# 11_PWR_SYS.net
KiCad netlist of a schematic drawn in Altium Designer
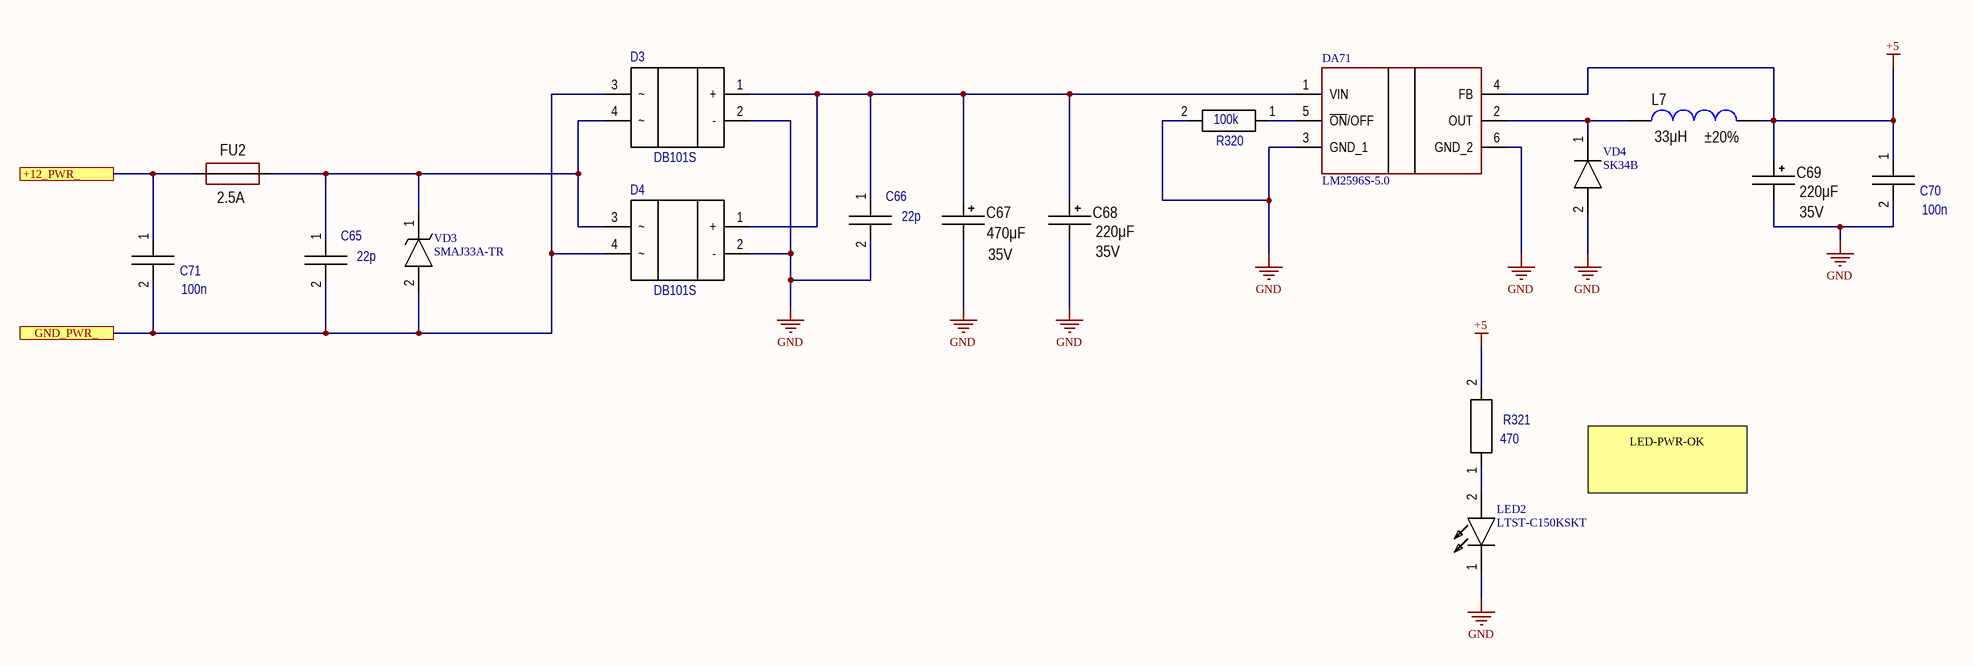
[diagram p0: 11_PWR_SYS.SchDoc]

(export (version "E")
  (design (tool "Eeschema 10.0.6"))
  (components
    (comp (ref "C65")
      (value "22p")
      (footprint "C0603")
      (fields
        (field (name "PART NUMBER") "GRM1885C1H220JA01D")
        (field (name "TOLERANCE") "±5%")
        (field (name "MANUFACTURER") "Murata Manufacturing")
      )
      (libsource (lib "AccessLibrary") (part "Capacitor"))
    )
    (comp (ref "C66")
      (value "22p")
      (footprint "C0603")
      (fields
        (field (name "PART NUMBER") "GRM1885C1H220JA01D")
        (field (name "TOLERANCE") "±5%")
        (field (name "MANUFACTURER") "Murata Manufacturing")
      )
      (libsource (lib "AccessLibrary") (part "Capacitor"))
    )
    (comp (ref "C67")
      (value "470μF")
      (footprint "board:CAP: D10C5H16")
      (description "ECAP (К50-35), 470мкФ, 35В, 105°C, 20%, 10x17мм P:5мм")
      (fields
        (field (name "MANUFACTURER") "JB Capacitors")
        (field (name "PARTNUMBER") "JRB1V471M05001000170000B")
        (field (name "VOLTAGE") "35V")
      )
      (libsource (lib "board") (part "Capacitors_Aluminium"))
    )
    (comp (ref "C68")
      (value "220μF")
      (footprint "board:CAP: D8C3.5H12")
      (description "ECAP (К50-35), 220мкФ, 35В, 105°C, 20%, 8x12мм P:3.5мм, Конденсатор электролитический алюминиевый")
      (fields
        (field (name "MANUFACTURER") "JB Capacitors")
        (field (name "PARTNUMBER") "JRB1V221M03500800120000B")
        (field (name "VOLTAGE") "35V")
      )
      (libsource (lib "board") (part "Capacitors_Aluminium"))
    )
    (comp (ref "C69")
      (value "220μF")
      (footprint "board:CAP: D8C3.5H12")
      (description "ECAP (К50-35), 220мкФ, 35В, 105°C, 20%, 8x12мм P:3.5мм, Конденсатор электролитический алюминиевый")
      (fields
        (field (name "MANUFACTURER") "JB Capacitors")
        (field (name "PARTNUMBER") "JRB1V221M03500800120000B")
        (field (name "VOLTAGE") "35V")
      )
      (libsource (lib "board") (part "Capacitors_Aluminium"))
    )
    (comp (ref "C70")
      (value "100n")
      (footprint "C0603")
      (fields
        (field (name "PART NUMBER") "GRM188R71C104KA01D")
        (field (name "TOLERANCE") "±10%")
        (field (name "MANUFACTURER") "Murata Manufacturing")
      )
      (libsource (lib "AccessLibrary") (part "Capacitor"))
    )
    (comp (ref "C71")
      (value "100n")
      (footprint "C0603")
      (fields
        (field (name "PART NUMBER") "GRM188R71C104KA01D")
        (field (name "TOLERANCE") "±10%")
        (field (name "MANUFACTURER") "Murata Manufacturing")
      )
      (libsource (lib "AccessLibrary") (part "Capacitor"))
    )
    (comp (ref "D3")
      (value "DB101S")
      (footprint "DB-1S")
      (description "SINGLE-PHASE SURFACE MOUNT BRIDGE RECTIFIER")
      (fields (field (name "COM") "DB101S") (field (name "MANUFACTURER") "DC COMPONENTS"))
      (libsource (lib "AccessLibrary") (part "DiodeBridge"))
    )
    (comp (ref "D4")
      (value "DB101S")
      (footprint "DB-1S")
      (description "SINGLE-PHASE SURFACE MOUNT BRIDGE RECTIFIER")
      (fields (field (name "COM") "DB101S") (field (name "MANUFACTURER") "DC COMPONENTS"))
      (libsource (lib "AccessLibrary") (part "DiodeBridge"))
    )
    (comp (ref "DA71")
      (value "LM2596S-5.0")
      (footprint "board:KTT0005B")
      (description "Integrated Circuit")
      (fields (field (name "MOUSER PART NUMBER") "926-LM2596S-50"))
      (libsource (lib "board") (part "LM2596S-5.0"))
    )
    (comp (ref "FU2")
      (value "~")
      (footprint "board:FUSE: 1206")
      (fields
        (field (name "MANUFACTURER") "046602.5NR")
        (field (name "VALUEMANUFACTURERPARTNUMBER") ", 13, 2.5A, 1206, ")
        (field (name "MAXCURRENT") "2.5A")
      )
      (libsource (lib "board") (part "Fuse"))
    )
    (comp (ref "L7")
      (value "33μH")
      (footprint "board:INDPM102100X400N")
      (description "CDRH104RNP-330NC")
      (fields
        (field (name "MANUFACTURER") "Sumida")
        (field (name "VALUEMANUFACTURERPARTNUMBER") "Fixed inductor, 33μH, ±20%, CDRH104RNP-330NC, 2.2A, -55...+125°C")
        (field (name "TOLERANCE") "±20%")
      )
      (libsource (lib "board") (part "Inductor_"))
    )
    (comp (ref "LED2")
      (value "LTST-C150KSKT")
      (footprint "board:LEDC3216X110N")
      (description "LED")
      (fields (field (name "MOUSER PART NUMBER") "859-LTST-C150KSKT"))
      (libsource (lib "board") (part "LTST-C150KSKT"))
    )
    (comp (ref "R320")
      (value "100k")
      (footprint "RESC1608N")
      (fields
        (field (name "PART NUMBER") "RC0603FK-07100KL")
        (field (name "TOLERANCE") "±1%")
        (field (name "MANUFACTURER") "Тайвань")
      )
      (libsource (lib "AccessLibrary") (part "Resistor"))
    )
    (comp (ref "R321")
      (value "470")
      (footprint "RESC1608N")
      (fields
        (field (name "PART NUMBER") "RC0603FK-07470RL")
        (field (name "TOLERANCE") "±1%")
        (field (name "MANUFACTURER") "Тайвань")
      )
      (libsource (lib "AccessLibrary") (part "Resistor"))
    )
    (comp (ref "VD3")
      (value "SMAJ33A-TR")
      (footprint "board:SM4T82AY")
      (description "TVS Diode (Uni-directional)")
      (fields (field (name "MOUSER PART NUMBER") "511-SMAJ33A-TR"))
      (libsource (lib "board") (part "SMAJ33A-TR"))
    )
    (comp (ref "VD4")
      (value "SK34B")
      (footprint "board:DIOM5236X261N")
      (description "Diode")
      (fields (field (name "PARTNUMBER") "SK34") (field (name "MOUSER PART NUMBER") "821-SK34B"))
      (libsource (lib "board") (part "SK34B"))
    )
  )
  (nets
    (net (code "1") (name "+5") (class "Default")
      (node (ref "C69") (pin "1") (pinfunction "1_1") (pintype "passive"))
      (node (ref "C70") (pin "1") (pinfunction "1_1") (pintype "passive"))
      (node (ref "DA71") (pin "4") (pinfunction "FB_4") (pintype "passive"))
      (node (ref "L7") (pin "1") (pinfunction "1_1") (pintype "passive"))
      (node (ref "R321") (pin "2") (pinfunction "2_2") (pintype "passive"))
    )
    (net (code "2") (name "/+12_PWR_") (class "Default")
      (node (ref "C71") (pin "1") (pinfunction "1_1") (pintype "passive"))
      (node (ref "FU2") (pin "1") (pinfunction "1_1") (pintype "passive"))
    )
    (net (code "3") (name "/GND_PWR_") (class "Default")
      (node (ref "C65") (pin "2") (pinfunction "2_2") (pintype "passive"))
      (node (ref "C71") (pin "2") (pinfunction "2_2") (pintype "passive"))
      (node (ref "D3") (pin "3") (pinfunction "~_3") (pintype "passive"))
      (node (ref "D4") (pin "4") (pinfunction "~_4") (pintype "passive"))
      (node (ref "VD3") (pin "2") (pinfunction "A_2") (pintype "passive"))
    )
    (net (code "4") (name "GND") (class "Default")
      (node (ref "C66") (pin "2") (pinfunction "2_2") (pintype "passive"))
      (node (ref "C67") (pin "2") (pinfunction "2_2") (pintype "passive"))
      (node (ref "C68") (pin "2") (pinfunction "2_2") (pintype "passive"))
      (node (ref "C69") (pin "2") (pinfunction "2_2") (pintype "passive"))
      (node (ref "C70") (pin "2") (pinfunction "2_2") (pintype "passive"))
      (node (ref "D3") (pin "2") (pinfunction "-_2") (pintype "passive"))
      (node (ref "D4") (pin "2") (pinfunction "-_2") (pintype "passive"))
      (node (ref "DA71") (pin "3") (pinfunction "GND_1_3") (pintype "passive"))
      (node (ref "DA71") (pin "6") (pinfunction "GND_2_6") (pintype "passive"))
      (node (ref "LED2") (pin "1") (pinfunction "K_1") (pintype "passive"))
      (node (ref "R320") (pin "2") (pinfunction "2_2") (pintype "passive"))
      (node (ref "VD4") (pin "2") (pinfunction "A_2") (pintype "passive"))
    )
    (net (code "5") (name "Net-(D3-+)") (class "Default")
      (node (ref "C66") (pin "1") (pinfunction "1_1") (pintype "passive"))
      (node (ref "C67") (pin "1") (pinfunction "1_1") (pintype "passive"))
      (node (ref "C68") (pin "1") (pinfunction "1_1") (pintype "passive"))
      (node (ref "D3") (pin "1") (pinfunction "+_1") (pintype "passive"))
      (node (ref "D4") (pin "1") (pinfunction "+_1") (pintype "passive"))
      (node (ref "DA71") (pin "1") (pinfunction "VIN_1") (pintype "passive"))
    )
    (net (code "6") (name "Net-(DA71-OUT)") (class "Default")
      (node (ref "DA71") (pin "2") (pinfunction "OUT_2") (pintype "passive"))
      (node (ref "L7") (pin "2") (pinfunction "2_2") (pintype "passive"))
      (node (ref "VD4") (pin "1") (pinfunction "K_1") (pintype "passive"))
    )
    (net (code "7") (name "Net-(DA71-~{ON}{slash}OFF)") (class "Default")
      (node (ref "DA71") (pin "5") (pinfunction "~{ON}/OFF_5") (pintype "passive"))
      (node (ref "R320") (pin "1") (pinfunction "1_1") (pintype "passive"))
    )
    (net (code "8") (name "Net-(LED2-A)") (class "Default")
      (node (ref "LED2") (pin "2") (pinfunction "A_2") (pintype "passive"))
      (node (ref "R321") (pin "1") (pinfunction "1_1") (pintype "passive"))
    )
    (net (code "9") (name "Net-(VD3-K)") (class "Default")
      (node (ref "C65") (pin "1") (pinfunction "1_1") (pintype "passive"))
      (node (ref "D3") (pin "4") (pinfunction "~_4") (pintype "passive"))
      (node (ref "D4") (pin "3") (pinfunction "~_3") (pintype "passive"))
      (node (ref "FU2") (pin "2") (pinfunction "2_2") (pintype "passive"))
      (node (ref "VD3") (pin "1") (pinfunction "K_1") (pintype "passive"))
    )
  )
)
